# LCD_SRAM.net
KiCad netlist of a schematic drawn in Altium Designer
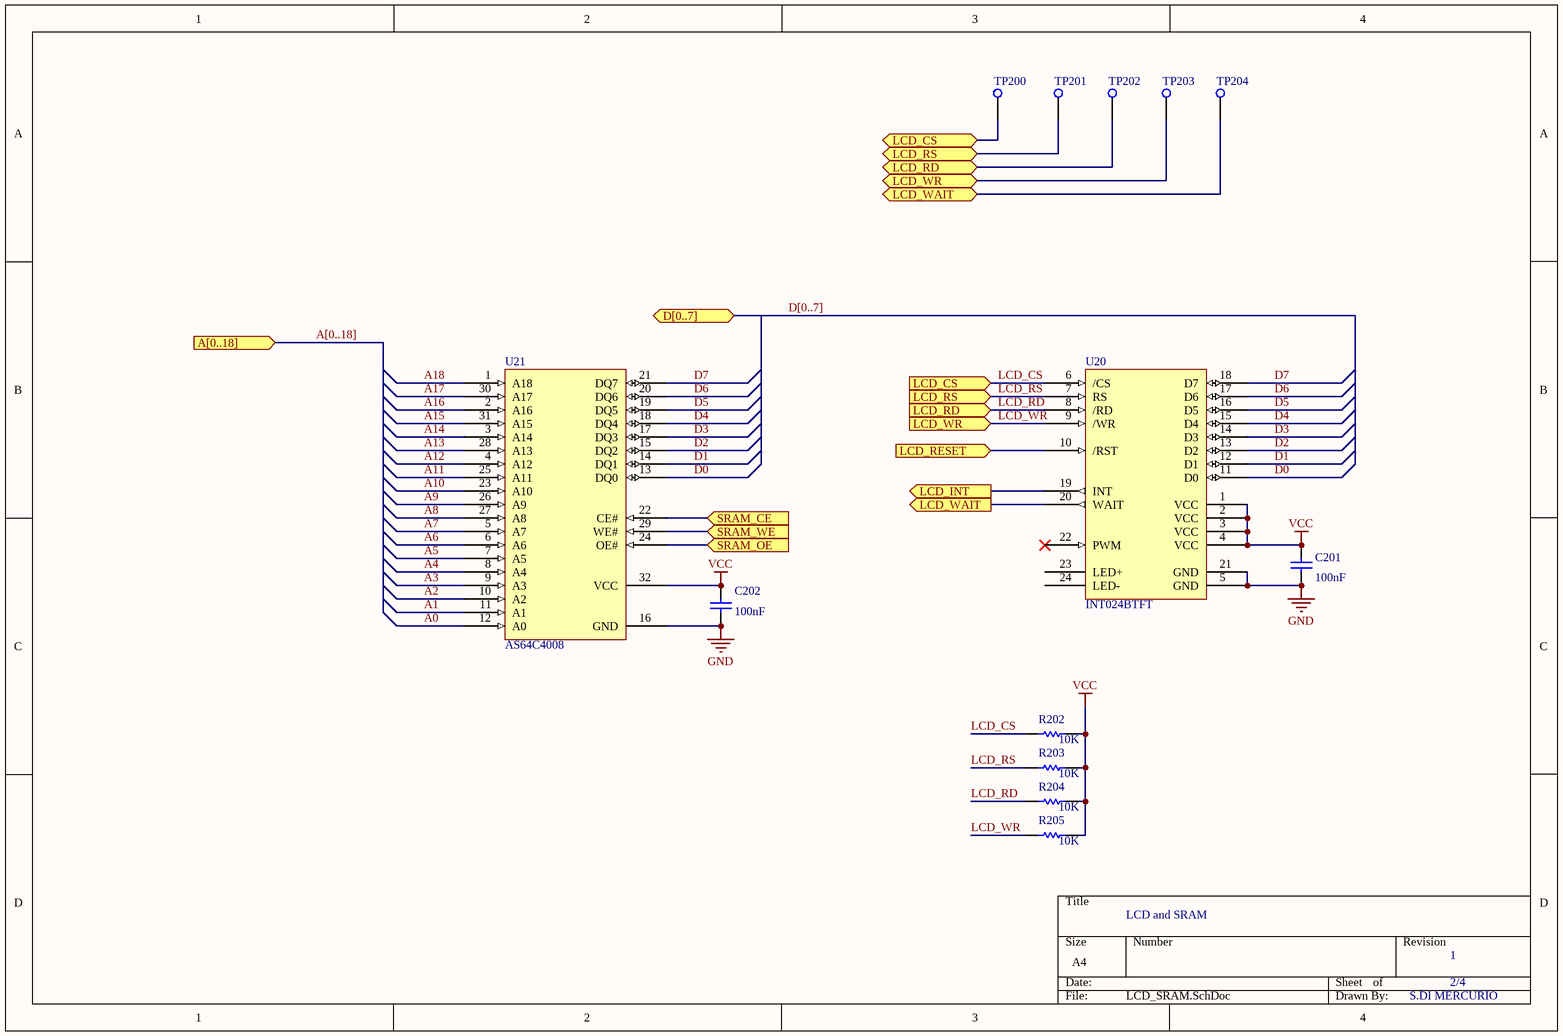
[diagram p0: LCD_SRAM.SchDoc]

(export (version "E")
  (design (tool "Eeschema 10.0.6"))
  (components
    (comp (ref "C201")
      (value "100nF")
      (footprint "CAPC1206(3216)100_N")
      (description "CAP 100nF 16V -20% to +80% 1206 (3216 Metric) Thickness 1mm SMD")
      (fields (field (name "TOLERANCE") "-20% to +80%") (field (name "Comment") "CAP 100nF 16V 1206(3216)"))
      (libsource (lib "Altium Content Vault") (part "CMP-1037-04185-1"))
    )
    (comp (ref "C202")
      (value "100nF")
      (footprint "CAPC1206(3216)100_N")
      (description "CAP 100nF 16V -20% to +80% 1206 (3216 Metric) Thickness 1mm SMD")
      (fields (field (name "TOLERANCE") "-20% to +80%") (field (name "Comment") "CAP 100nF 16V 1206(3216)"))
      (libsource (lib "Altium Content Vault") (part "CMP-1037-04185-1"))
    )
    (comp (ref "R202")
      (value "10K")
      (footprint "RESC1206(3216)_L")
      (description "10K 0.25W 1% 1206 (3216 Metric)  SMD")
      (fields (field (name "POWER") "0.25 W") (field (name "TOLERANCE") "1 %"))
      (libsource (lib "Altium Content Vault") (part "CMP-1014-00623-1"))
    )
    (comp (ref "R203")
      (value "10K")
      (footprint "RESC1206(3216)_L")
      (description "10K 0.25W 1% 1206 (3216 Metric)  SMD")
      (fields (field (name "POWER") "0.25 W") (field (name "TOLERANCE") "1 %"))
      (libsource (lib "Altium Content Vault") (part "CMP-1014-00623-1"))
    )
    (comp (ref "R204")
      (value "10K")
      (footprint "RESC1206(3216)_L")
      (description "10K 0.25W 1% 1206 (3216 Metric)  SMD")
      (fields (field (name "POWER") "0.25 W") (field (name "TOLERANCE") "1 %"))
      (libsource (lib "Altium Content Vault") (part "CMP-1014-00623-1"))
    )
    (comp (ref "R205")
      (value "10K")
      (footprint "RESC1206(3216)_L")
      (description "10K 0.25W 1% 1206 (3216 Metric)  SMD")
      (fields (field (name "POWER") "0.25 W") (field (name "TOLERANCE") "1 %"))
      (libsource (lib "Altium Content Vault") (part "CMP-1014-00623-1"))
    )
    (comp (ref "TP200")
      (value "TestPoint")
      (footprint "TP1")
      (description "TestPoint SMD")
      (libsource (lib "INSA") (part "TestPoint"))
    )
    (comp (ref "TP201")
      (value "TestPoint")
      (footprint "TP1")
      (description "TestPoint SMD")
      (libsource (lib "INSA") (part "TestPoint"))
    )
    (comp (ref "TP202")
      (value "TestPoint")
      (footprint "TP1")
      (description "TestPoint SMD")
      (libsource (lib "INSA") (part "TestPoint"))
    )
    (comp (ref "TP203")
      (value "TestPoint")
      (footprint "TP1")
      (description "TestPoint SMD")
      (libsource (lib "INSA") (part "TestPoint"))
    )
    (comp (ref "TP204")
      (value "TestPoint")
      (footprint "TP1")
      (description "TestPoint SMD")
      (libsource (lib "INSA") (part "TestPoint"))
    )
    (comp (ref "U20")
      (value "INT024BTFT")
      (footprint "INT024BTFT")
      (libsource (lib "INSA") (part "LCD INT024BTFT"))
    )
    (comp (ref "U21")
      (value "AS64C4008")
      (footprint "SOP32")
      (description "SRAM 4Mbits 512K*8Bits 55 ns")
      (libsource (lib "INSA") (part "AS64C4008"))
    )
  )
  (nets
    (net (code "1") (name "/A0") (class "Default")
      (node (ref "U21") (pin "12") (pinfunction "A0_12") (pintype "input"))
    )
    (net (code "2") (name "/A1") (class "Default")
      (node (ref "U21") (pin "11") (pinfunction "A1_11") (pintype "input"))
    )
    (net (code "3") (name "/A2") (class "Default")
      (node (ref "U21") (pin "10") (pinfunction "A2_10") (pintype "input"))
    )
    (net (code "4") (name "/A3") (class "Default")
      (node (ref "U21") (pin "9") (pinfunction "A3_9") (pintype "input"))
    )
    (net (code "5") (name "/A4") (class "Default")
      (node (ref "U21") (pin "8") (pinfunction "A4_8") (pintype "input"))
    )
    (net (code "6") (name "/A5") (class "Default")
      (node (ref "U21") (pin "7") (pinfunction "A5_7") (pintype "input"))
    )
    (net (code "7") (name "/A6") (class "Default")
      (node (ref "U21") (pin "6") (pinfunction "A6_6") (pintype "input"))
    )
    (net (code "8") (name "/A7") (class "Default")
      (node (ref "U21") (pin "5") (pinfunction "A7_5") (pintype "input"))
    )
    (net (code "9") (name "/A8") (class "Default")
      (node (ref "U21") (pin "27") (pinfunction "A8_27") (pintype "input"))
    )
    (net (code "10") (name "/A9") (class "Default")
      (node (ref "U21") (pin "26") (pinfunction "A9_26") (pintype "input"))
    )
    (net (code "11") (name "/A10") (class "Default")
      (node (ref "U21") (pin "23") (pinfunction "A10_23") (pintype "input"))
    )
    (net (code "12") (name "/A11") (class "Default")
      (node (ref "U21") (pin "25") (pinfunction "A11_25") (pintype "input"))
    )
    (net (code "13") (name "/A12") (class "Default")
      (node (ref "U21") (pin "4") (pinfunction "A12_4") (pintype "input"))
    )
    (net (code "14") (name "/A13") (class "Default")
      (node (ref "U21") (pin "28") (pinfunction "A13_28") (pintype "input"))
    )
    (net (code "15") (name "/A14") (class "Default")
      (node (ref "U21") (pin "3") (pinfunction "A14_3") (pintype "input"))
    )
    (net (code "16") (name "/A15") (class "Default")
      (node (ref "U21") (pin "31") (pinfunction "A15_31") (pintype "input"))
    )
    (net (code "17") (name "/A16") (class "Default")
      (node (ref "U21") (pin "2") (pinfunction "A16_2") (pintype "input"))
    )
    (net (code "18") (name "/A17") (class "Default")
      (node (ref "U21") (pin "30") (pinfunction "A17_30") (pintype "input"))
    )
    (net (code "19") (name "/A18") (class "Default")
      (node (ref "U21") (pin "1") (pinfunction "A18_1") (pintype "input"))
    )
    (net (code "21") (name "/D0") (class "Default")
      (node (ref "U20") (pin "11") (pinfunction "D0_11") (pintype "bidirectional"))
      (node (ref "U21") (pin "13") (pinfunction "DQ0_13") (pintype "bidirectional"))
    )
    (net (code "22") (name "/D1") (class "Default")
      (node (ref "U20") (pin "12") (pinfunction "D1_12") (pintype "bidirectional"))
      (node (ref "U21") (pin "14") (pinfunction "DQ1_14") (pintype "bidirectional"))
    )
    (net (code "23") (name "/D2") (class "Default")
      (node (ref "U20") (pin "13") (pinfunction "D2_13") (pintype "bidirectional"))
      (node (ref "U21") (pin "15") (pinfunction "DQ2_15") (pintype "bidirectional"))
    )
    (net (code "24") (name "/D3") (class "Default")
      (node (ref "U20") (pin "14") (pinfunction "D3_14") (pintype "bidirectional"))
      (node (ref "U21") (pin "17") (pinfunction "DQ3_17") (pintype "bidirectional"))
    )
    (net (code "25") (name "/D4") (class "Default")
      (node (ref "U20") (pin "15") (pinfunction "D4_15") (pintype "bidirectional"))
      (node (ref "U21") (pin "18") (pinfunction "DQ4_18") (pintype "bidirectional"))
    )
    (net (code "26") (name "/D5") (class "Default")
      (node (ref "U20") (pin "16") (pinfunction "D5_16") (pintype "bidirectional"))
      (node (ref "U21") (pin "19") (pinfunction "DQ5_19") (pintype "bidirectional"))
    )
    (net (code "27") (name "/D6") (class "Default")
      (node (ref "U20") (pin "17") (pinfunction "D6_17") (pintype "bidirectional"))
      (node (ref "U21") (pin "20") (pinfunction "DQ6_20") (pintype "bidirectional"))
    )
    (net (code "28") (name "/D7") (class "Default")
      (node (ref "U20") (pin "18") (pinfunction "D7_18") (pintype "bidirectional"))
      (node (ref "U21") (pin "21") (pinfunction "DQ7_21") (pintype "bidirectional"))
    )
    (net (code "30") (name "/LCD_CS") (class "Default")
      (node (ref "R202") (pin "2") (pinfunction "2_2") (pintype "passive"))
      (node (ref "TP200") (pin "1") (pinfunction "1_1") (pintype "passive"))
      (node (ref "U20") (pin "6") (pinfunction "/CS_6") (pintype "input"))
    )
    (net (code "31") (name "/LCD_INT") (class "Default")
      (node (ref "U20") (pin "19") (pinfunction "INT_19") (pintype "output"))
    )
    (net (code "32") (name "/LCD_RD") (class "Default")
      (node (ref "R204") (pin "2") (pinfunction "2_2") (pintype "passive"))
      (node (ref "TP202") (pin "1") (pinfunction "1_1") (pintype "passive"))
      (node (ref "U20") (pin "8") (pinfunction "/RD_8") (pintype "input"))
    )
    (net (code "33") (name "/LCD_RESET") (class "Default")
      (node (ref "U20") (pin "10") (pinfunction "/RST_10") (pintype "input"))
    )
    (net (code "34") (name "/LCD_RS") (class "Default")
      (node (ref "R203") (pin "2") (pinfunction "2_2") (pintype "passive"))
      (node (ref "TP201") (pin "1") (pinfunction "1_1") (pintype "passive"))
      (node (ref "U20") (pin "7") (pinfunction "RS_7") (pintype "input"))
    )
    (net (code "35") (name "/LCD_WAIT") (class "Default")
      (node (ref "TP204") (pin "1") (pinfunction "1_1") (pintype "passive"))
      (node (ref "U20") (pin "20") (pinfunction "WAIT_20") (pintype "output"))
    )
    (net (code "36") (name "/LCD_WR") (class "Default")
      (node (ref "R205") (pin "2") (pinfunction "2_2") (pintype "passive"))
      (node (ref "TP203") (pin "1") (pinfunction "1_1") (pintype "passive"))
      (node (ref "U20") (pin "9") (pinfunction "/WR_9") (pintype "input"))
    )
    (net (code "37") (name "/SRAM_CE") (class "Default")
      (node (ref "U21") (pin "22") (pinfunction "CE#_22") (pintype "input"))
    )
    (net (code "38") (name "/SRAM_OE") (class "Default")
      (node (ref "U21") (pin "24") (pinfunction "OE#_24") (pintype "input"))
    )
    (net (code "39") (name "/SRAM_WE") (class "Default")
      (node (ref "U21") (pin "29") (pinfunction "WE#_29") (pintype "input"))
    )
    (net (code "40") (name "GND") (class "Default")
      (node (ref "C201") (pin "2") (pinfunction "2_2") (pintype "passive"))
      (node (ref "C202") (pin "2") (pinfunction "2_2") (pintype "passive"))
      (node (ref "U20") (pin "21") (pinfunction "GND_21") (pintype "power_in"))
      (node (ref "U20") (pin "5") (pinfunction "GND_5") (pintype "power_in"))
      (node (ref "U21") (pin "16") (pinfunction "GND_16") (pintype "power_in"))
    )
    (net (code "41") (name "VCC") (class "Default")
      (node (ref "C201") (pin "1") (pinfunction "1_1") (pintype "passive"))
      (node (ref "C202") (pin "1") (pinfunction "1_1") (pintype "passive"))
      (node (ref "R202") (pin "1") (pinfunction "1_1") (pintype "passive"))
      (node (ref "R203") (pin "1") (pinfunction "1_1") (pintype "passive"))
      (node (ref "R204") (pin "1") (pinfunction "1_1") (pintype "passive"))
      (node (ref "R205") (pin "1") (pinfunction "1_1") (pintype "passive"))
      (node (ref "U20") (pin "1") (pinfunction "VCC_1") (pintype "power_in"))
      (node (ref "U20") (pin "2") (pinfunction "VCC_2") (pintype "power_in"))
      (node (ref "U20") (pin "3") (pinfunction "VCC_3") (pintype "power_in"))
      (node (ref "U20") (pin "4") (pinfunction "VCC_4") (pintype "power_in"))
      (node (ref "U21") (pin "32") (pinfunction "VCC_32") (pintype "power_in"))
    )
    (net (code "42") (name "unconnected-(U20-LED+-Pad23)") (class "Default")
      (node (ref "U20") (pin "23") (pinfunction "LED+_23") (pintype "passive"))
    )
    (net (code "43") (name "unconnected-(U20-LED--Pad24)") (class "Default")
      (node (ref "U20") (pin "24") (pinfunction "LED-_24") (pintype "passive"))
    )
    (net (code "44") (name "unconnected-(U20-PWM-Pad22)") (class "Default")
      (node (ref "U20") (pin "22") (pinfunction "PWM_22") (pintype "input+no_connect"))
    )
  )
)
